# CommPosition_V1_0_Mar2016.net
KiCad netlist of a schematic drawn in EAGLE
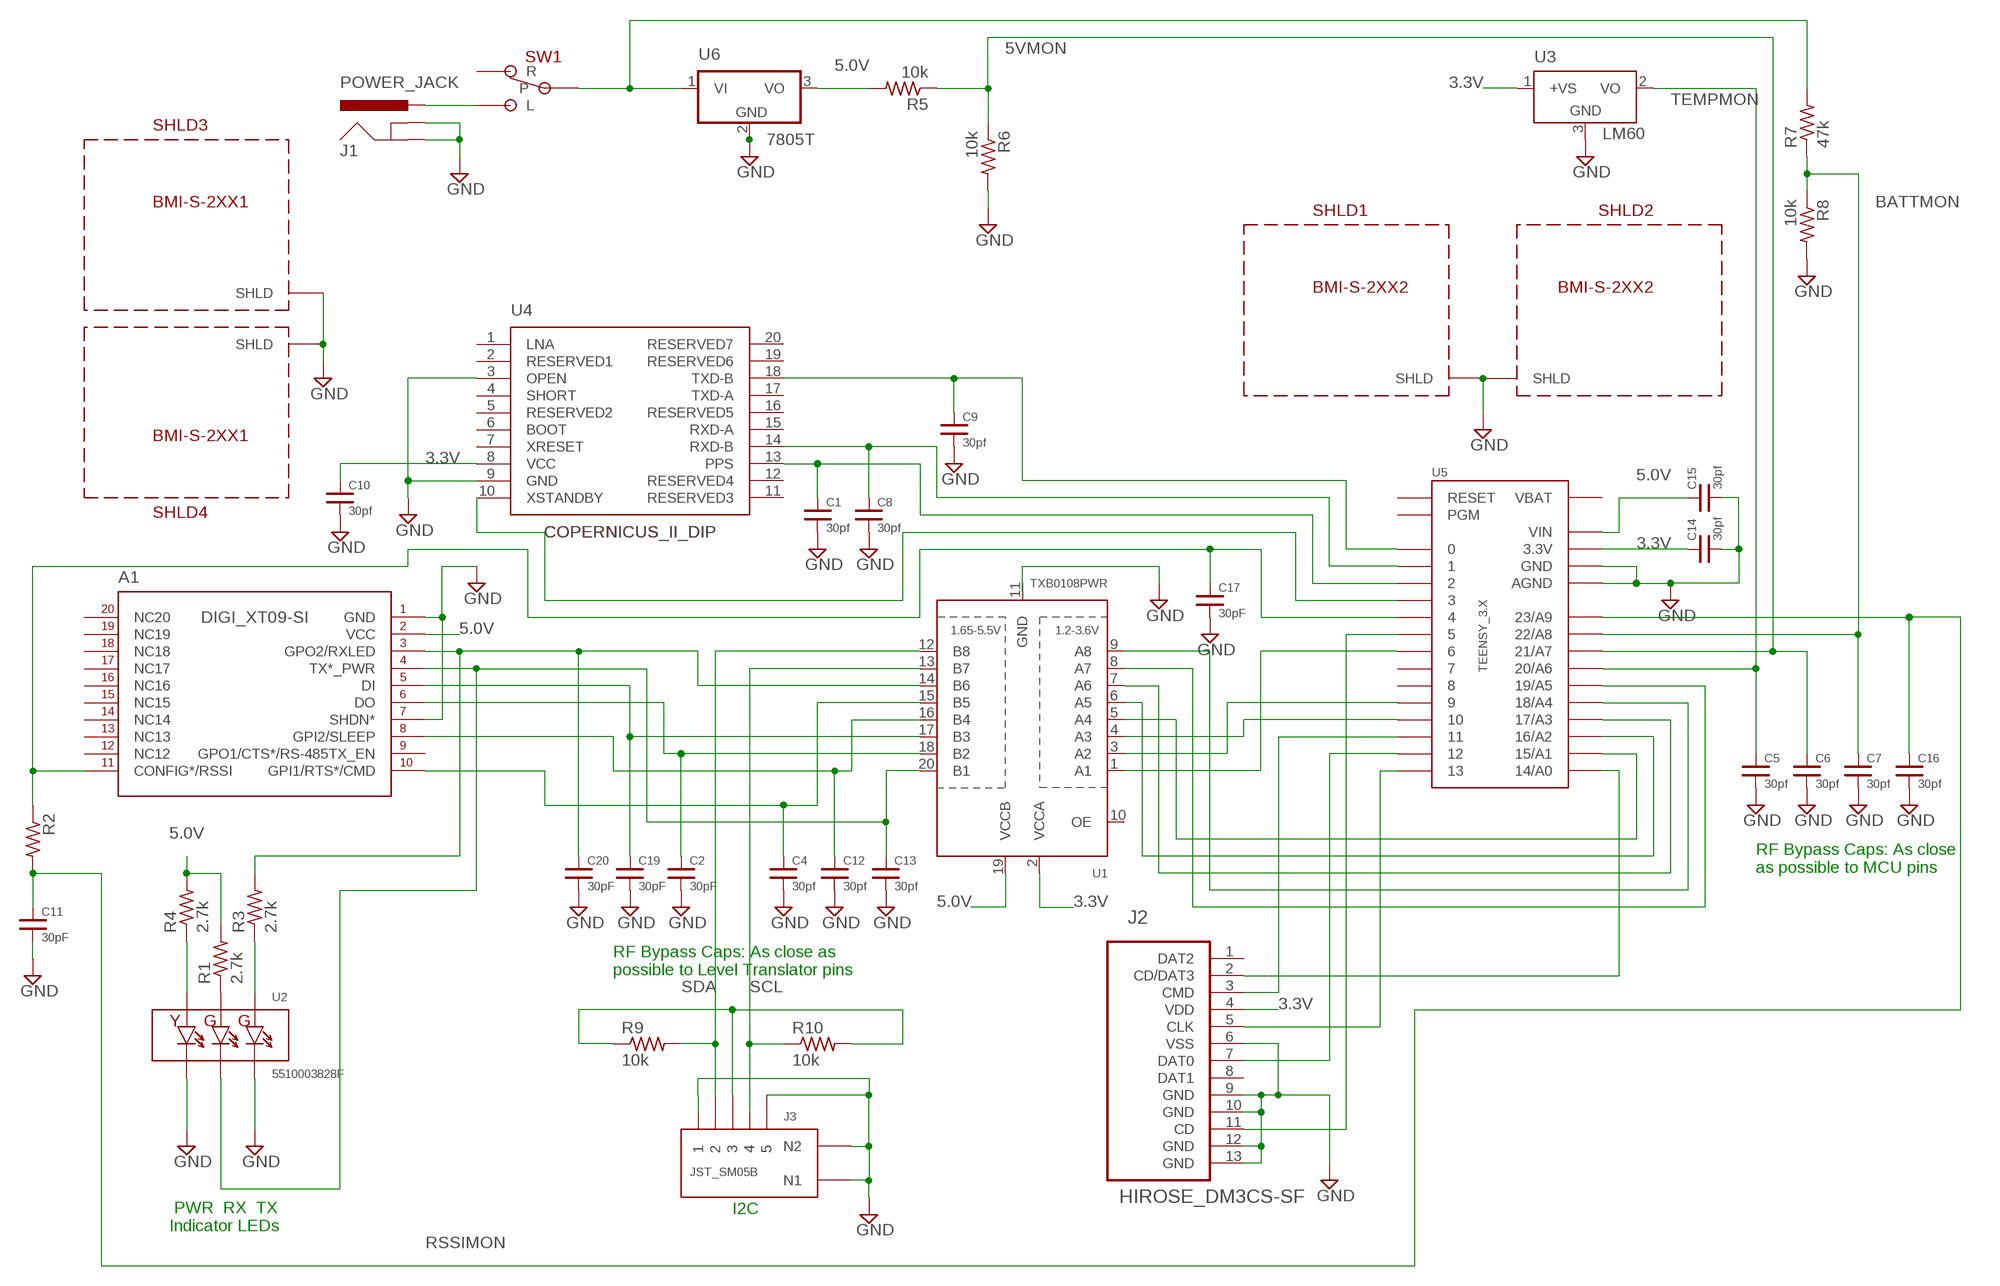
[diagram p0: schematic, sheet 1]

(export (version "E")
  (design (tool "Eeschema 10.0.6"))
  (components
    (comp (ref "A1")
      (value "DIGI_XT09-SI")
      (footprint "eagle-import:DIGI_XT09-SI")
      (libsource (lib "eagle-import") (part "DIGI_XT09-SI"))
    )
    (comp (ref "C1")
      (value "30pf")
      (footprint "eagle-import:C0603")
      (libsource (lib "eagle-import") (part "C-USC0603"))
    )
    (comp (ref "C2")
      (value "30pF")
      (footprint "eagle-import:C0603")
      (libsource (lib "eagle-import") (part "C-USC0603"))
    )
    (comp (ref "C4")
      (value "30pf")
      (footprint "eagle-import:C0603")
      (libsource (lib "eagle-import") (part "C-USC0603"))
    )
    (comp (ref "C5")
      (value "30pf")
      (footprint "eagle-import:C0603")
      (libsource (lib "eagle-import") (part "C-USC0603"))
    )
    (comp (ref "C6")
      (value "30pf")
      (footprint "eagle-import:C0603")
      (libsource (lib "eagle-import") (part "C-USC0603"))
    )
    (comp (ref "C7")
      (value "30pf")
      (footprint "eagle-import:C0603")
      (libsource (lib "eagle-import") (part "C-USC0603"))
    )
    (comp (ref "C8")
      (value "30pf")
      (footprint "eagle-import:C0603")
      (libsource (lib "eagle-import") (part "C-USC0603"))
    )
    (comp (ref "C9")
      (value "30pf")
      (footprint "eagle-import:C0603")
      (libsource (lib "eagle-import") (part "C-USC0603"))
    )
    (comp (ref "C10")
      (value "30pf")
      (footprint "eagle-import:C0603")
      (libsource (lib "eagle-import") (part "C-USC0603"))
    )
    (comp (ref "C11")
      (value "30pF")
      (footprint "eagle-import:C0603")
      (libsource (lib "eagle-import") (part "C-USC0603"))
    )
    (comp (ref "C12")
      (value "30pf")
      (footprint "eagle-import:C0603")
      (libsource (lib "eagle-import") (part "C-USC0603"))
    )
    (comp (ref "C13")
      (value "30pf")
      (footprint "eagle-import:C0603")
      (libsource (lib "eagle-import") (part "C-USC0603"))
    )
    (comp (ref "C14")
      (value "30pf")
      (footprint "eagle-import:C0603")
      (libsource (lib "eagle-import") (part "C-USC0603"))
    )
    (comp (ref "C15")
      (value "30pf")
      (footprint "eagle-import:C0603")
      (libsource (lib "eagle-import") (part "C-USC0603"))
    )
    (comp (ref "C16")
      (value "30pf")
      (footprint "eagle-import:C0603")
      (libsource (lib "eagle-import") (part "C-USC0603"))
    )
    (comp (ref "C17")
      (value "30pF")
      (footprint "eagle-import:C0603")
      (libsource (lib "eagle-import") (part "C-USC0603"))
    )
    (comp (ref "C19")
      (value "30pF")
      (footprint "eagle-import:C0603")
      (libsource (lib "eagle-import") (part "C-USC0603"))
    )
    (comp (ref "C20")
      (value "30pF")
      (footprint "eagle-import:C0603")
      (libsource (lib "eagle-import") (part "C-USC0603"))
    )
    (comp (ref "J1")
      (value "POWER_JACK")
      (footprint "eagle-import:PWR_JACK_BB")
      (libsource (lib "eagle-import") (part "POWER_JACK"))
    )
    (comp (ref "J2")
      (value "HIROSE_DM3CS-SF")
      (footprint "eagle-import:HIROSE_DM3CS-SF")
      (fields (field (name "MPN") "DM3CS-SF"))
      (libsource (lib "eagle-import") (part "HIROSE_DM3CS-SF"))
    )
    (comp (ref "J3")
      (value "JST_SM05B")
      (footprint "eagle-import:JST_SM05B")
      (libsource (lib "eagle-import") (part "JST_SM05B"))
    )
    (comp (ref "R1")
      (value "2.7k")
      (footprint "eagle-import:R0805")
      (libsource (lib "eagle-import") (part "R-US_R0805"))
    )
    (comp (ref "R2")
      (value "R-US_R0805")
      (footprint "eagle-import:R0805")
      (libsource (lib "eagle-import") (part "R-US_R0805"))
    )
    (comp (ref "R3")
      (value "2.7k")
      (footprint "eagle-import:R0805")
      (libsource (lib "eagle-import") (part "R-US_R0805"))
    )
    (comp (ref "R4")
      (value "2.7k")
      (footprint "eagle-import:R0805")
      (libsource (lib "eagle-import") (part "R-US_R0805"))
    )
    (comp (ref "R5")
      (value "10k")
      (footprint "eagle-import:R0805")
      (libsource (lib "eagle-import") (part "R-US_R0805"))
    )
    (comp (ref "R6")
      (value "10k")
      (footprint "eagle-import:R0805")
      (libsource (lib "eagle-import") (part "R-US_R0805"))
    )
    (comp (ref "R7")
      (value "47k")
      (footprint "eagle-import:R0805")
      (libsource (lib "eagle-import") (part "R-US_R0805"))
    )
    (comp (ref "R8")
      (value "10k")
      (footprint "eagle-import:R0805")
      (libsource (lib "eagle-import") (part "R-US_R0805"))
    )
    (comp (ref "R9")
      (value "10k")
      (footprint "eagle-import:R0805")
      (libsource (lib "eagle-import") (part "R-US_R0805"))
    )
    (comp (ref "R10")
      (value "10k")
      (footprint "eagle-import:R0805")
      (libsource (lib "eagle-import") (part "R-US_R0805"))
    )
    (comp (ref "SHLD1")
      (value "BMI-S-2XX2")
      (footprint "eagle-import:BMI-S-207-F")
      (libsource (lib "eagle-import") (part "BMI-S-2XX2"))
    )
    (comp (ref "SHLD2")
      (value "BMI-S-2XX2")
      (footprint "eagle-import:BMI-S-207-F")
      (libsource (lib "eagle-import") (part "BMI-S-2XX2"))
    )
    (comp (ref "SHLD3")
      (value "BMI-S-2XX1")
      (footprint "eagle-import:BMI-S-206-F")
      (libsource (lib "eagle-import") (part "BMI-S-2XX1"))
    )
    (comp (ref "SHLD4")
      (value "BMI-S-2XX1")
      (footprint "eagle-import:BMI-S-206-F")
      (libsource (lib "eagle-import") (part "BMI-S-2XX1"))
    )
    (comp (ref "SW1")
      (value "SPDT_RA_3A")
      (footprint "eagle-import:ESWITCH_SPDT_RA")
      (libsource (lib "eagle-import") (part "SPDT_RA_3A"))
    )
    (comp (ref "U1")
      (value "TXB0108PWR")
      (footprint "eagle-import:TSSOP20")
      (libsource (lib "eagle-import") (part "TXB0108PWR"))
    )
    (comp (ref "U2")
      (value "5510003828F")
      (footprint "eagle-import:TRIPLE_LED_SIDE_0.1IN")
      (libsource (lib "eagle-import") (part "5510003828F"))
    )
    (comp (ref "U3")
      (value "LM60")
      (footprint "eagle-import:TO92")
      (libsource (lib "eagle-import") (part "LM60"))
    )
    (comp (ref "U4")
      (value "COPERNICUS_II_DIP")
      (footprint "eagle-import:COPERNICUS_II_DIP")
      (libsource (lib "eagle-import") (part "COPERNICUS_II_DIP"))
    )
    (comp (ref "U5")
      (value "TEENSY_3.X")
      (footprint "eagle-import:TEENSY_3.X_PERIPHERY")
      (libsource (lib "eagle-import") (part "TEENSY_3.X"))
    )
    (comp (ref "U6")
      (value "7805T")
      (footprint "eagle-import:TO220H")
      (libsource (lib "eagle-import") (part "78T05"))
    )
  )
  (nets
    (net (code "1") (name "/3.3V") (class "Default")
      (node (ref "C10") (pin "1") (pinfunction "1_1") (pintype "passive"))
      (node (ref "C14") (pin "1") (pinfunction "1_1") (pintype "passive"))
      (node (ref "J2") (pin "4") (pinfunction "VDD_4") (pintype "passive"))
      (node (ref "U1") (pin "2") (pinfunction "VCCA_2") (pintype "bidirectional"))
      (node (ref "U3") (pin "1") (pinfunction "+VS_1") (pintype "input"))
      (node (ref "U4") (pin "8") (pinfunction "VCC_8") (pintype "bidirectional"))
      (node (ref "U5") (pin "3.3V") (pinfunction "3.3V_3.3V") (pintype "power_in"))
      (node (ref "U5") (pin "3.3V1") (pinfunction "3.3V_3.3V1") (pintype "power_in"))
    )
    (net (code "2") (name "/5.0V") (class "Default")
      (node (ref "A1") (pin "P$2") (pinfunction "VCC_P$2") (pintype "power_in"))
      (node (ref "C15") (pin "1") (pinfunction "1_1") (pintype "passive"))
      (node (ref "R1") (pin "2") (pinfunction "2_2") (pintype "passive"))
      (node (ref "R4") (pin "2") (pinfunction "2_2") (pintype "passive"))
      (node (ref "R5") (pin "2") (pinfunction "2_2") (pintype "passive"))
      (node (ref "U1") (pin "19") (pinfunction "VCCB_19") (pintype "bidirectional"))
      (node (ref "U5") (pin "VIN") (pinfunction "VIN_VIN") (pintype "input"))
      (node (ref "U6") (pin "3") (pinfunction "VO_3") (pintype "passive"))
    )
    (net (code "3") (name "/5VMON") (class "Default")
      (node (ref "C6") (pin "1") (pinfunction "1_1") (pintype "passive"))
      (node (ref "R5") (pin "1") (pinfunction "1_1") (pintype "passive"))
      (node (ref "R6") (pin "1") (pinfunction "1_1") (pintype "passive"))
      (node (ref "U5") (pin "21/A7") (pinfunction "21/A7_21/A7") (pintype "bidirectional"))
    )
    (net (code "4") (name "/BATTMON") (class "Default")
      (node (ref "C7") (pin "1") (pinfunction "1_1") (pintype "passive"))
      (node (ref "R7") (pin "1") (pinfunction "1_1") (pintype "passive"))
      (node (ref "R8") (pin "1") (pinfunction "1_1") (pintype "passive"))
      (node (ref "U5") (pin "22/A8") (pinfunction "22/A8_22/A8") (pintype "bidirectional"))
    )
    (net (code "5") (name "/RSSIMON") (class "Default")
      (node (ref "C11") (pin "1") (pinfunction "1_1") (pintype "passive"))
      (node (ref "C16") (pin "1") (pinfunction "1_1") (pintype "passive"))
      (node (ref "R2") (pin "2") (pinfunction "2_2") (pintype "passive"))
      (node (ref "U5") (pin "23/A9") (pinfunction "23/A9_23/A9") (pintype "bidirectional"))
    )
    (net (code "6") (name "/SCL") (class "Default")
      (node (ref "J3") (pin "P$4") (pinfunction "4_P$4") (pintype "bidirectional"))
      (node (ref "R10") (pin "1") (pinfunction "1_1") (pintype "passive"))
      (node (ref "U1") (pin "13") (pinfunction "B7_13") (pintype "bidirectional"))
    )
    (net (code "7") (name "/SDA") (class "Default")
      (node (ref "J3") (pin "P$2") (pinfunction "2_P$2") (pintype "bidirectional"))
      (node (ref "R9") (pin "2") (pinfunction "2_2") (pintype "passive"))
      (node (ref "U1") (pin "12") (pinfunction "B8_12") (pintype "bidirectional"))
    )
    (net (code "8") (name "/TEMPMON") (class "Default")
      (node (ref "C5") (pin "1") (pinfunction "1_1") (pintype "passive"))
      (node (ref "U3") (pin "2") (pinfunction "VO_2") (pintype "input"))
      (node (ref "U5") (pin "20/A6") (pinfunction "20/A6_20/A6") (pintype "bidirectional"))
    )
    (net (code "9") (name "GND") (class "Default")
      (node (ref "A1") (pin "P$1") (pinfunction "GND_P$1") (pintype "power_in"))
      (node (ref "A1") (pin "P$21") (pinfunction "GND_P$21") (pintype "power_in"))
      (node (ref "A1") (pin "P$22") (pinfunction "GND_P$22") (pintype "power_in"))
      (node (ref "A1") (pin "P$23") (pinfunction "GND_P$23") (pintype "power_in"))
      (node (ref "A1") (pin "P$24") (pinfunction "GND_P$24") (pintype "power_in"))
      (node (ref "A1") (pin "P$7") (pinfunction "SHDN*_P$7") (pintype "input"))
      (node (ref "C1") (pin "2") (pinfunction "2_2") (pintype "passive"))
      (node (ref "C10") (pin "2") (pinfunction "2_2") (pintype "passive"))
      (node (ref "C11") (pin "2") (pinfunction "2_2") (pintype "passive"))
      (node (ref "C12") (pin "2") (pinfunction "2_2") (pintype "passive"))
      (node (ref "C13") (pin "2") (pinfunction "2_2") (pintype "passive"))
      (node (ref "C14") (pin "2") (pinfunction "2_2") (pintype "passive"))
      (node (ref "C15") (pin "2") (pinfunction "2_2") (pintype "passive"))
      (node (ref "C16") (pin "2") (pinfunction "2_2") (pintype "passive"))
      (node (ref "C17") (pin "2") (pinfunction "2_2") (pintype "passive"))
      (node (ref "C19") (pin "2") (pinfunction "2_2") (pintype "passive"))
      (node (ref "C2") (pin "2") (pinfunction "2_2") (pintype "passive"))
      (node (ref "C20") (pin "2") (pinfunction "2_2") (pintype "passive"))
      (node (ref "C4") (pin "2") (pinfunction "2_2") (pintype "passive"))
      (node (ref "C5") (pin "2") (pinfunction "2_2") (pintype "passive"))
      (node (ref "C6") (pin "2") (pinfunction "2_2") (pintype "passive"))
      (node (ref "C7") (pin "2") (pinfunction "2_2") (pintype "passive"))
      (node (ref "C8") (pin "2") (pinfunction "2_2") (pintype "passive"))
      (node (ref "C9") (pin "2") (pinfunction "2_2") (pintype "passive"))
      (node (ref "J1") (pin "GND") (pinfunction "GND_GND") (pintype "bidirectional"))
      (node (ref "J1") (pin "GNDBREAK") (pinfunction "GNDBREAK_GNDBREAK") (pintype "bidirectional"))
      (node (ref "J2") (pin "10") (pinfunction "GND_10") (pintype "passive"))
      (node (ref "J2") (pin "12") (pinfunction "GND_12") (pintype "passive"))
      (node (ref "J2") (pin "13") (pinfunction "GND_13") (pintype "passive"))
      (node (ref "J2") (pin "6") (pinfunction "VSS_6") (pintype "passive"))
      (node (ref "J2") (pin "9") (pinfunction "GND_9") (pintype "passive"))
      (node (ref "J3") (pin "P$1") (pinfunction "1_P$1") (pintype "bidirectional"))
      (node (ref "J3") (pin "P$5") (pinfunction "5_P$5") (pintype "bidirectional"))
      (node (ref "J3") (pin "P$6") (pinfunction "N1_P$6") (pintype "bidirectional"))
      (node (ref "J3") (pin "P$7") (pinfunction "N2_P$7") (pintype "bidirectional"))
      (node (ref "R6") (pin "2") (pinfunction "2_2") (pintype "passive"))
      (node (ref "R8") (pin "2") (pinfunction "2_2") (pintype "passive"))
      (node (ref "SHLD1") (pin "P$10") (pinfunction "SHLD_P$10") (pintype "bidirectional"))
      (node (ref "SHLD1") (pin "P$11") (pinfunction "SHLD_P$11") (pintype "bidirectional"))
      (node (ref "SHLD1") (pin "P$12") (pinfunction "SHLD_P$12") (pintype "bidirectional"))
      (node (ref "SHLD1") (pin "P$14") (pinfunction "SHLD_P$14") (pintype "bidirectional"))
      (node (ref "SHLD1") (pin "P$15") (pinfunction "SHLD_P$15") (pintype "bidirectional"))
      (node (ref "SHLD1") (pin "P$16") (pinfunction "SHLD_P$16") (pintype "bidirectional"))
      (node (ref "SHLD1") (pin "P$17") (pinfunction "SHLD_P$17") (pintype "bidirectional"))
      (node (ref "SHLD1") (pin "P$18") (pinfunction "SHLD_P$18") (pintype "bidirectional"))
      (node (ref "SHLD1") (pin "P$19") (pinfunction "SHLD_P$19") (pintype "bidirectional"))
      (node (ref "SHLD1") (pin "P$2") (pinfunction "SHLD_P$2") (pintype "bidirectional"))
      (node (ref "SHLD1") (pin "P$20") (pinfunction "SHLD_P$20") (pintype "bidirectional"))
      (node (ref "SHLD1") (pin "P$21") (pinfunction "SHLD_P$21") (pintype "bidirectional"))
      (node (ref "SHLD1") (pin "P$22") (pinfunction "SHLD_P$22") (pintype "bidirectional"))
      (node (ref "SHLD1") (pin "P$23") (pinfunction "SHLD_P$23") (pintype "bidirectional"))
      (node (ref "SHLD1") (pin "P$24") (pinfunction "SHLD_P$24") (pintype "bidirectional"))
      (node (ref "SHLD1") (pin "P$25") (pinfunction "SHLD_P$25") (pintype "bidirectional"))
      (node (ref "SHLD1") (pin "P$26") (pinfunction "SHLD_P$26") (pintype "bidirectional"))
      (node (ref "SHLD1") (pin "P$27") (pinfunction "SHLD_P$27") (pintype "bidirectional"))
      (node (ref "SHLD1") (pin "P$28") (pinfunction "SHLD_P$28") (pintype "bidirectional"))
      (node (ref "SHLD1") (pin "P$29") (pinfunction "SHLD_P$29") (pintype "bidirectional"))
      (node (ref "SHLD1") (pin "P$3") (pinfunction "SHLD_P$3") (pintype "bidirectional"))
      (node (ref "SHLD1") (pin "P$30") (pinfunction "SHLD_P$30") (pintype "bidirectional"))
      (node (ref "SHLD1") (pin "P$31") (pinfunction "SHLD_P$31") (pintype "bidirectional"))
      (node (ref "SHLD1") (pin "P$32") (pinfunction "SHLD_P$32") (pintype "bidirectional"))
      (node (ref "SHLD1") (pin "P$33") (pinfunction "SHLD_P$33") (pintype "bidirectional"))
      (node (ref "SHLD1") (pin "P$34") (pinfunction "SHLD_P$34") (pintype "bidirectional"))
      (node (ref "SHLD1") (pin "P$4") (pinfunction "SHLD_P$4") (pintype "bidirectional"))
      (node (ref "SHLD1") (pin "P$5") (pinfunction "SHLD_P$5") (pintype "bidirectional"))
      (node (ref "SHLD1") (pin "P$6") (pinfunction "SHLD_P$6") (pintype "bidirectional"))
      (node (ref "SHLD1") (pin "P$7") (pinfunction "SHLD_P$7") (pintype "bidirectional"))
      (node (ref "SHLD1") (pin "P$8") (pinfunction "SHLD_P$8") (pintype "bidirectional"))
      (node (ref "SHLD1") (pin "P$9") (pinfunction "SHLD_P$9") (pintype "bidirectional"))
      (node (ref "SHLD2") (pin "P$10") (pinfunction "SHLD_P$10") (pintype "bidirectional"))
      (node (ref "SHLD2") (pin "P$11") (pinfunction "SHLD_P$11") (pintype "bidirectional"))
      (node (ref "SHLD2") (pin "P$12") (pinfunction "SHLD_P$12") (pintype "bidirectional"))
      (node (ref "SHLD2") (pin "P$14") (pinfunction "SHLD_P$14") (pintype "bidirectional"))
      (node (ref "SHLD2") (pin "P$15") (pinfunction "SHLD_P$15") (pintype "bidirectional"))
      (node (ref "SHLD2") (pin "P$16") (pinfunction "SHLD_P$16") (pintype "bidirectional"))
      (node (ref "SHLD2") (pin "P$17") (pinfunction "SHLD_P$17") (pintype "bidirectional"))
      (node (ref "SHLD2") (pin "P$18") (pinfunction "SHLD_P$18") (pintype "bidirectional"))
      (node (ref "SHLD2") (pin "P$19") (pinfunction "SHLD_P$19") (pintype "bidirectional"))
      (node (ref "SHLD2") (pin "P$2") (pinfunction "SHLD_P$2") (pintype "bidirectional"))
      (node (ref "SHLD2") (pin "P$20") (pinfunction "SHLD_P$20") (pintype "bidirectional"))
      (node (ref "SHLD2") (pin "P$21") (pinfunction "SHLD_P$21") (pintype "bidirectional"))
      (node (ref "SHLD2") (pin "P$22") (pinfunction "SHLD_P$22") (pintype "bidirectional"))
      (node (ref "SHLD2") (pin "P$23") (pinfunction "SHLD_P$23") (pintype "bidirectional"))
      (node (ref "SHLD2") (pin "P$24") (pinfunction "SHLD_P$24") (pintype "bidirectional"))
      (node (ref "SHLD2") (pin "P$25") (pinfunction "SHLD_P$25") (pintype "bidirectional"))
      (node (ref "SHLD2") (pin "P$26") (pinfunction "SHLD_P$26") (pintype "bidirectional"))
      (node (ref "SHLD2") (pin "P$27") (pinfunction "SHLD_P$27") (pintype "bidirectional"))
      (node (ref "SHLD2") (pin "P$28") (pinfunction "SHLD_P$28") (pintype "bidirectional"))
      (node (ref "SHLD2") (pin "P$29") (pinfunction "SHLD_P$29") (pintype "bidirectional"))
      (node (ref "SHLD2") (pin "P$3") (pinfunction "SHLD_P$3") (pintype "bidirectional"))
      (node (ref "SHLD2") (pin "P$30") (pinfunction "SHLD_P$30") (pintype "bidirectional"))
      (node (ref "SHLD2") (pin "P$31") (pinfunction "SHLD_P$31") (pintype "bidirectional"))
      (node (ref "SHLD2") (pin "P$32") (pinfunction "SHLD_P$32") (pintype "bidirectional"))
      (node (ref "SHLD2") (pin "P$33") (pinfunction "SHLD_P$33") (pintype "bidirectional"))
      (node (ref "SHLD2") (pin "P$34") (pinfunction "SHLD_P$34") (pintype "bidirectional"))
      (node (ref "SHLD2") (pin "P$4") (pinfunction "SHLD_P$4") (pintype "bidirectional"))
      (node (ref "SHLD2") (pin "P$5") (pinfunction "SHLD_P$5") (pintype "bidirectional"))
      (node (ref "SHLD2") (pin "P$6") (pinfunction "SHLD_P$6") (pintype "bidirectional"))
      (node (ref "SHLD2") (pin "P$7") (pinfunction "SHLD_P$7") (pintype "bidirectional"))
      (node (ref "SHLD2") (pin "P$8") (pinfunction "SHLD_P$8") (pintype "bidirectional"))
      (node (ref "SHLD2") (pin "P$9") (pinfunction "SHLD_P$9") (pintype "bidirectional"))
      (node (ref "SHLD3") (pin "P$1") (pinfunction "SHLD_P$1") (pintype "bidirectional"))
      (node (ref "SHLD3") (pin "P$10") (pinfunction "SHLD_P$10") (pintype "bidirectional"))
      (node (ref "SHLD3") (pin "P$11") (pinfunction "SHLD_P$11") (pintype "bidirectional"))
      (node (ref "SHLD3") (pin "P$12") (pinfunction "SHLD_P$12") (pintype "bidirectional"))
      (node (ref "SHLD3") (pin "P$14") (pinfunction "SHLD_P$14") (pintype "bidirectional"))
      (node (ref "SHLD3") (pin "P$15") (pinfunction "SHLD_P$15") (pintype "bidirectional"))
      (node (ref "SHLD3") (pin "P$16") (pinfunction "SHLD_P$16") (pintype "bidirectional"))
      (node (ref "SHLD3") (pin "P$17") (pinfunction "SHLD_P$17") (pintype "bidirectional"))
      (node (ref "SHLD3") (pin "P$18") (pinfunction "SHLD_P$18") (pintype "bidirectional"))
      (node (ref "SHLD3") (pin "P$2") (pinfunction "SHLD_P$2") (pintype "bidirectional"))
      (node (ref "SHLD3") (pin "P$21") (pinfunction "SHLD_P$21") (pintype "bidirectional"))
      (node (ref "SHLD3") (pin "P$22") (pinfunction "SHLD_P$22") (pintype "bidirectional"))
      (node (ref "SHLD3") (pin "P$23") (pinfunction "SHLD_P$23") (pintype "bidirectional"))
      (node (ref "SHLD3") (pin "P$24") (pinfunction "SHLD_P$24") (pintype "bidirectional"))
      (node (ref "SHLD3") (pin "P$25") (pinfunction "SHLD_P$25") (pintype "bidirectional"))
      (node (ref "SHLD3") (pin "P$3") (pinfunction "SHLD_P$3") (pintype "bidirectional"))
      (node (ref "SHLD3") (pin "P$31") (pinfunction "SHLD_P$31") (pintype "bidirectional"))
      (node (ref "SHLD3") (pin "P$32") (pinfunction "SHLD_P$32") (pintype "bidirectional"))
      (node (ref "SHLD3") (pin "P$4") (pinfunction "SHLD_P$4") (pintype "bidirectional"))
      (node (ref "SHLD3") (pin "P$5") (pinfunction "SHLD_P$5") (pintype "bidirectional"))
      (node (ref "SHLD3") (pin "P$6") (pinfunction "SHLD_P$6") (pintype "bidirectional"))
      (node (ref "SHLD3") (pin "P$7") (pinfunction "SHLD_P$7") (pintype "bidirectional"))
      (node (ref "SHLD3") (pin "P$8") (pinfunction "SHLD_P$8") (pintype "bidirectional"))
      (node (ref "SHLD3") (pin "P$9") (pinfunction "SHLD_P$9") (pintype "bidirectional"))
      (node (ref "SHLD4") (pin "P$1") (pinfunction "SHLD_P$1") (pintype "bidirectional"))
      (node (ref "SHLD4") (pin "P$10") (pinfunction "SHLD_P$10") (pintype "bidirectional"))
      (node (ref "SHLD4") (pin "P$11") (pinfunction "SHLD_P$11") (pintype "bidirectional"))
      (node (ref "SHLD4") (pin "P$12") (pinfunction "SHLD_P$12") (pintype "bidirectional"))
      (node (ref "SHLD4") (pin "P$14") (pinfunction "SHLD_P$14") (pintype "bidirectional"))
      (node (ref "SHLD4") (pin "P$15") (pinfunction "SHLD_P$15") (pintype "bidirectional"))
      (node (ref "SHLD4") (pin "P$16") (pinfunction "SHLD_P$16") (pintype "bidirectional"))
      (node (ref "SHLD4") (pin "P$17") (pinfunction "SHLD_P$17") (pintype "bidirectional"))
      (node (ref "SHLD4") (pin "P$18") (pinfunction "SHLD_P$18") (pintype "bidirectional"))
      (node (ref "SHLD4") (pin "P$2") (pinfunction "SHLD_P$2") (pintype "bidirectional"))
      (node (ref "SHLD4") (pin "P$21") (pinfunction "SHLD_P$21") (pintype "bidirectional"))
      (node (ref "SHLD4") (pin "P$22") (pinfunction "SHLD_P$22") (pintype "bidirectional"))
      (node (ref "SHLD4") (pin "P$23") (pinfunction "SHLD_P$23") (pintype "bidirectional"))
      (node (ref "SHLD4") (pin "P$24") (pinfunction "SHLD_P$24") (pintype "bidirectional"))
      (node (ref "SHLD4") (pin "P$25") (pinfunction "SHLD_P$25") (pintype "bidirectional"))
      (node (ref "SHLD4") (pin "P$3") (pinfunction "SHLD_P$3") (pintype "bidirectional"))
      (node (ref "SHLD4") (pin "P$31") (pinfunction "SHLD_P$31") (pintype "bidirectional"))
      (node (ref "SHLD4") (pin "P$32") (pinfunction "SHLD_P$32") (pintype "bidirectional"))
      (node (ref "SHLD4") (pin "P$4") (pinfunction "SHLD_P$4") (pintype "bidirectional"))
      (node (ref "SHLD4") (pin "P$5") (pinfunction "SHLD_P$5") (pintype "bidirectional"))
      (node (ref "SHLD4") (pin "P$6") (pinfunction "SHLD_P$6") (pintype "bidirectional"))
      (node (ref "SHLD4") (pin "P$7") (pinfunction "SHLD_P$7") (pintype "bidirectional"))
      (node (ref "SHLD4") (pin "P$8") (pinfunction "SHLD_P$8") (pintype "bidirectional"))
      (node (ref "SHLD4") (pin "P$9") (pinfunction "SHLD_P$9") (pintype "bidirectional"))
      (node (ref "U1") (pin "11") (pinfunction "GND_11") (pintype "bidirectional"))
      (node (ref "U2") (pin "P$1") (pinfunction "1_P$1") (pintype "bidirectional"))
      (node (ref "U2") (pin "P$5") (pinfunction "5_P$5") (pintype "bidirectional"))
      (node (ref "U3") (pin "3") (pinfunction "GND_3") (pintype "power_in"))
      (node (ref "U4") (pin "3") (pinfunction "OPEN_3") (pintype "bidirectional"))
      (node (ref "U4") (pin "9") (pinfunction "GND_9") (pintype "bidirectional"))
      (node (ref "U5") (pin "AGND") (pinfunction "AGND_AGND") (pintype "power_in"))
      (node (ref "U5") (pin "GND") (pinfunction "GND_GND") (pintype "power_in"))
      (node (ref "U5") (pin "GND1") (pinfunction "GND_GND1") (pintype "power_in"))
      (node (ref "U6") (pin "2") (pinfunction "GND_2") (pintype "passive"))
    )
    (net (code "10") (name "Net-(A1-CONFIG*{slash}RSSI)") (class "Default")
      (node (ref "A1") (pin "P$11") (pinfunction "CONFIG*/RSSI_P$11") (pintype "bidirectional"))
      (node (ref "C17") (pin "1") (pinfunction "1_1") (pintype "passive"))
      (node (ref "R2") (pin "1") (pinfunction "1_1") (pintype "passive"))
      (node (ref "U5") (pin "4") (pinfunction "4_4") (pintype "bidirectional"))
    )
    (net (code "11") (name "Net-(A1-DI)") (class "Default")
      (node (ref "A1") (pin "P$5") (pinfunction "DI_P$5") (pintype "bidirectional"))
      (node (ref "C19") (pin "1") (pinfunction "1_1") (pintype "passive"))
      (node (ref "U1") (pin "17") (pinfunction "B3_17") (pintype "bidirectional"))
    )
    (net (code "12") (name "Net-(A1-DO)") (class "Default")
      (node (ref "A1") (pin "P$6") (pinfunction "DO_P$6") (pintype "output"))
      (node (ref "C2") (pin "1") (pinfunction "1_1") (pintype "passive"))
      (node (ref "U1") (pin "18") (pinfunction "B2_18") (pintype "bidirectional"))
    )
    (net (code "13") (name "Net-(A1-GPI1{slash}RTS*{slash}CMD)") (class "Default")
      (node (ref "A1") (pin "P$10") (pinfunction "GPI1/RTS*/CMD_P$10") (pintype "input"))
      (node (ref "C4") (pin "1") (pinfunction "1_1") (pintype "passive"))
      (node (ref "U1") (pin "15") (pinfunction "B5_15") (pintype "bidirectional"))
    )
    (net (code "14") (name "Net-(A1-GPI2{slash}SLEEP)") (class "Default")
      (node (ref "A1") (pin "P$8") (pinfunction "GPI2/SLEEP_P$8") (pintype "input"))
      (node (ref "C12") (pin "1") (pinfunction "1_1") (pintype "passive"))
      (node (ref "U1") (pin "16") (pinfunction "B4_16") (pintype "bidirectional"))
    )
    (net (code "15") (name "Net-(A1-GPO2{slash}RXLED)") (class "Default")
      (node (ref "A1") (pin "P$3") (pinfunction "GPO2/RXLED_P$3") (pintype "input"))
      (node (ref "C20") (pin "1") (pinfunction "1_1") (pintype "passive"))
      (node (ref "R3") (pin "2") (pinfunction "2_2") (pintype "passive"))
      (node (ref "U1") (pin "14") (pinfunction "B6_14") (pintype "bidirectional"))
    )
    (net (code "16") (name "Net-(A1-TX*_PWR)") (class "Default")
      (node (ref "A1") (pin "P$4") (pinfunction "TX*_PWR_P$4") (pintype "output"))
      (node (ref "C13") (pin "1") (pinfunction "1_1") (pintype "passive"))
      (node (ref "U1") (pin "20") (pinfunction "B1_20") (pintype "bidirectional"))
      (node (ref "U2") (pin "P$3") (pinfunction "3_P$3") (pintype "bidirectional"))
    )
    (net (code "17") (name "Net-(J2-CD)") (class "Default")
      (node (ref "J2") (pin "11") (pinfunction "CD_11") (pintype "passive"))
      (node (ref "U5") (pin "5") (pinfunction "5_5") (pintype "bidirectional"))
    )
    (net (code "18") (name "Net-(J2-CD{slash}DAT3)") (class "Default")
      (node (ref "J2") (pin "2") (pinfunction "CD/DAT3_2") (pintype "passive"))
      (node (ref "U5") (pin "14/A0") (pinfunction "14/A0_14/A0") (pintype "bidirectional"))
    )
    (net (code "19") (name "Net-(J2-CLK)") (class "Default")
      (node (ref "J2") (pin "5") (pinfunction "CLK_5") (pintype "passive"))
      (node (ref "U5") (pin "13") (pinfunction "13_13") (pintype "bidirectional"))
    )
    (net (code "20") (name "Net-(J2-CMD)") (class "Default")
      (node (ref "J2") (pin "3") (pinfunction "CMD_3") (pintype "passive"))
      (node (ref "U5") (pin "11") (pinfunction "11_11") (pintype "bidirectional"))
    )
    (net (code "21") (name "Net-(J2-DAT0)") (class "Default")
      (node (ref "J2") (pin "7") (pinfunction "DAT0_7") (pintype "passive"))
      (node (ref "U5") (pin "12") (pinfunction "12_12") (pintype "bidirectional"))
    )
    (net (code "22") (name "Net-(J3-3)") (class "Default")
      (node (ref "J3") (pin "P$3") (pinfunction "3_P$3") (pintype "bidirectional"))
      (node (ref "R10") (pin "2") (pinfunction "2_2") (pintype "passive"))
      (node (ref "R9") (pin "1") (pinfunction "1_1") (pintype "passive"))
    )
    (net (code "23") (name "Net-(SW1-L)") (class "Default")
      (node (ref "J1") (pin "PWR") (pinfunction "PWR_PWR") (pintype "bidirectional"))
      (node (ref "SW1") (pin "P$1") (pinfunction "L_P$1") (pintype "bidirectional"))
    )
    (net (code "24") (name "Net-(SW1-P)") (class "Default")
      (node (ref "R7") (pin "2") (pinfunction "2_2") (pintype "passive"))
      (node (ref "SW1") (pin "P$2") (pinfunction "P_P$2") (pintype "bidirectional"))
      (node (ref "U6") (pin "1") (pinfunction "VI_1") (pintype "input"))
    )
    (net (code "25") (name "Net-(U1-A1)") (class "Default")
      (node (ref "U1") (pin "1") (pinfunction "A1_1") (pintype "bidirectional"))
      (node (ref "U5") (pin "6") (pinfunction "6_6") (pintype "bidirectional"))
    )
    (net (code "26") (name "Net-(U1-A2)") (class "Default")
      (node (ref "U1") (pin "3") (pinfunction "A2_3") (pintype "bidirectional"))
      (node (ref "U5") (pin "9") (pinfunction "9_9") (pintype "bidirectional"))
    )
    (net (code "27") (name "Net-(U1-A3)") (class "Default")
      (node (ref "U1") (pin "4") (pinfunction "A3_4") (pintype "bidirectional"))
      (node (ref "U5") (pin "10") (pinfunction "10_10") (pintype "bidirectional"))
    )
    (net (code "28") (name "Net-(U1-A4)") (class "Default")
      (node (ref "U1") (pin "5") (pinfunction "A4_5") (pintype "bidirectional"))
      (node (ref "U5") (pin "15/A1") (pinfunction "15/A1_15/A1") (pintype "bidirectional"))
    )
    (net (code "29") (name "Net-(U1-A5)") (class "Default")
      (node (ref "U1") (pin "6") (pinfunction "A5_6") (pintype "bidirectional"))
      (node (ref "U5") (pin "16/A2") (pinfunction "16/A2_16/A2") (pintype "bidirectional"))
    )
    (net (code "30") (name "Net-(U1-A6)") (class "Default")
      (node (ref "U1") (pin "7") (pinfunction "A6_7") (pintype "bidirectional"))
      (node (ref "U5") (pin "17/A3") (pinfunction "17/A3_17/A3") (pintype "bidirectional"))
    )
    (net (code "31") (name "Net-(U1-A7)") (class "Default")
      (node (ref "U1") (pin "8") (pinfunction "A7_8") (pintype "bidirectional"))
      (node (ref "U5") (pin "19/A5") (pinfunction "19/A5_19/A5") (pintype "bidirectional"))
    )
    (net (code "32") (name "Net-(U1-A8)") (class "Default")
      (node (ref "U1") (pin "9") (pinfunction "A8_9") (pintype "bidirectional"))
      (node (ref "U5") (pin "18/A4") (pinfunction "18/A4_18/A4") (pintype "bidirectional"))
    )
    (net (code "33") (name "Net-(U2-2)") (class "Default")
      (node (ref "R3") (pin "1") (pinfunction "1_1") (pintype "passive"))
      (node (ref "U2") (pin "P$2") (pinfunction "2_P$2") (pintype "bidirectional"))
    )
    (net (code "34") (name "Net-(U2-4)") (class "Default")
      (node (ref "R1") (pin "1") (pinfunction "1_1") (pintype "passive"))
      (node (ref "U2") (pin "P$4") (pinfunction "4_P$4") (pintype "bidirectional"))
    )
    (net (code "35") (name "Net-(U2-6)") (class "Default")
      (node (ref "R4") (pin "1") (pinfunction "1_1") (pintype "passive"))
      (node (ref "U2") (pin "P$6") (pinfunction "6_P$6") (pintype "bidirectional"))
    )
    (net (code "36") (name "Net-(U4-PPS)") (class "Default")
      (node (ref "C1") (pin "1") (pinfunction "1_1") (pintype "passive"))
      (node (ref "U4") (pin "13") (pinfunction "PPS_13") (pintype "bidirectional"))
      (node (ref "U5") (pin "2") (pinfunction "2_2") (pintype "bidirectional"))
    )
    (net (code "37") (name "Net-(U4-RXD-B)") (class "Default")
      (node (ref "C8") (pin "1") (pinfunction "1_1") (pintype "passive"))
      (node (ref "U4") (pin "14") (pinfunction "RXD-B_14") (pintype "bidirectional"))
      (node (ref "U5") (pin "1") (pinfunction "1_1") (pintype "bidirectional"))
    )
    (net (code "38") (name "Net-(U4-TXD-B)") (class "Default")
      (node (ref "C9") (pin "1") (pinfunction "1_1") (pintype "passive"))
      (node (ref "U4") (pin "18") (pinfunction "TXD-B_18") (pintype "bidirectional"))
      (node (ref "U5") (pin "0") (pinfunction "0_0") (pintype "bidirectional"))
    )
    (net (code "39") (name "Net-(U4-XSTANDBY)") (class "Default")
      (node (ref "U4") (pin "10") (pinfunction "XSTANDBY_10") (pintype "bidirectional"))
      (node (ref "U5") (pin "3") (pinfunction "3_3") (pintype "bidirectional"))
    )
    (net (code "40") (name "unconnected-(A1-GPO1{slash}CTS*{slash}RS-485TX_EN-PadP$9)") (class "Default")
      (node (ref "A1") (pin "P$9") (pinfunction "GPO1/CTS*/RS-485TX_EN_P$9") (pintype "output"))
    )
    (net (code "41") (name "unconnected-(A1-NC12-PadP$12)") (class "Default")
      (node (ref "A1") (pin "P$12") (pinfunction "NC12_P$12") (pintype "no_connect"))
    )
    (net (code "42") (name "unconnected-(A1-NC13-PadP$13)") (class "Default")
      (node (ref "A1") (pin "P$13") (pinfunction "NC13_P$13") (pintype "no_connect"))
    )
    (net (code "43") (name "unconnected-(A1-NC14-PadP$14)") (class "Default")
      (node (ref "A1") (pin "P$14") (pinfunction "NC14_P$14") (pintype "no_connect"))
    )
    (net (code "44") (name "unconnected-(A1-NC15-PadP$15)") (class "Default")
      (node (ref "A1") (pin "P$15") (pinfunction "NC15_P$15") (pintype "no_connect"))
    )
    (net (code "45") (name "unconnected-(A1-NC16-PadP$16)") (class "Default")
      (node (ref "A1") (pin "P$16") (pinfunction "NC16_P$16") (pintype "no_connect"))
    )
    (net (code "46") (name "unconnected-(A1-NC17-PadP$17)") (class "Default")
      (node (ref "A1") (pin "P$17") (pinfunction "NC17_P$17") (pintype "no_connect"))
    )
    (net (code "47") (name "unconnected-(A1-NC18-PadP$18)") (class "Default")
      (node (ref "A1") (pin "P$18") (pinfunction "NC18_P$18") (pintype "no_connect"))
    )
    (net (code "48") (name "unconnected-(A1-NC19-PadP$19)") (class "Default")
      (node (ref "A1") (pin "P$19") (pinfunction "NC19_P$19") (pintype "no_connect"))
    )
    (net (code "49") (name "unconnected-(A1-NC20-PadP$20)") (class "Default")
      (node (ref "A1") (pin "P$20") (pinfunction "NC20_P$20") (pintype "no_connect"))
    )
    (net (code "50") (name "unconnected-(J2-DAT1-Pad8)") (class "Default")
      (node (ref "J2") (pin "8") (pinfunction "DAT1_8") (pintype "passive"))
    )
    (net (code "51") (name "unconnected-(J2-DAT2-Pad1)") (class "Default")
      (node (ref "J2") (pin "1") (pinfunction "DAT2_1") (pintype "passive"))
    )
    (net (code "52") (name "unconnected-(SW1-R-PadP$3)") (class "Default")
      (node (ref "SW1") (pin "P$3") (pinfunction "R_P$3") (pintype "bidirectional"))
    )
    (net (code "53") (name "unconnected-(U1-OE-Pad10)") (class "Default")
      (node (ref "U1") (pin "10") (pinfunction "OE_10") (pintype "bidirectional"))
    )
    (net (code "54") (name "unconnected-(U4-BOOT-Pad6)") (class "Default")
      (node (ref "U4") (pin "6") (pinfunction "BOOT_6") (pintype "bidirectional"))
    )
    (net (code "55") (name "unconnected-(U4-LNA-Pad1)") (class "Default")
      (node (ref "U4") (pin "1") (pinfunction "LNA_1") (pintype "bidirectional"))
    )
    (net (code "56") (name "unconnected-(U4-RESERVED1-Pad2)") (class "Default")
      (node (ref "U4") (pin "2") (pinfunction "RESERVED1_2") (pintype "bidirectional"))
    )
    (net (code "57") (name "unconnected-(U4-RESERVED2-Pad5)") (class "Default")
      (node (ref "U4") (pin "5") (pinfunction "RESERVED2_5") (pintype "bidirectional"))
    )
    (net (code "58") (name "unconnected-(U4-RESERVED3-Pad11)") (class "Default")
      (node (ref "U4") (pin "11") (pinfunction "RESERVED3_11") (pintype "bidirectional"))
    )
    (net (code "59") (name "unconnected-(U4-RESERVED4-Pad12)") (class "Default")
      (node (ref "U4") (pin "12") (pinfunction "RESERVED4_12") (pintype "bidirectional"))
    )
    (net (code "60") (name "unconnected-(U4-RESERVED5-Pad16)") (class "Default")
      (node (ref "U4") (pin "16") (pinfunction "RESERVED5_16") (pintype "bidirectional"))
    )
    (net (code "61") (name "unconnected-(U4-RESERVED6-Pad19)") (class "Default")
      (node (ref "U4") (pin "19") (pinfunction "RESERVED6_19") (pintype "bidirectional"))
    )
    (net (code "62") (name "unconnected-(U4-RESERVED7-Pad20)") (class "Default")
      (node (ref "U4") (pin "20") (pinfunction "RESERVED7_20") (pintype "bidirectional"))
    )
    (net (code "63") (name "unconnected-(U4-RXD-A-Pad15)") (class "Default")
      (node (ref "U4") (pin "15") (pinfunction "RXD-A_15") (pintype "bidirectional"))
    )
    (net (code "64") (name "unconnected-(U4-SHORT-Pad4)") (class "Default")
      (node (ref "U4") (pin "4") (pinfunction "SHORT_4") (pintype "bidirectional"))
    )
    (net (code "65") (name "unconnected-(U4-TXD-A-Pad17)") (class "Default")
      (node (ref "U4") (pin "17") (pinfunction "TXD-A_17") (pintype "bidirectional"))
    )
    (net (code "66") (name "unconnected-(U4-XRESET-Pad7)") (class "Default")
      (node (ref "U4") (pin "7") (pinfunction "XRESET_7") (pintype "bidirectional"))
    )
    (net (code "67") (name "unconnected-(U5-Pad7)") (class "Default")
      (node (ref "U5") (pin "7") (pinfunction "7_7") (pintype "bidirectional"))
    )
    (net (code "68") (name "unconnected-(U5-Pad8)") (class "Default")
      (node (ref "U5") (pin "8") (pinfunction "8_8") (pintype "bidirectional"))
    )
    (net (code "69") (name "unconnected-(U5-PadPGM)") (class "Default")
      (node (ref "U5") (pin "PGM") (pinfunction "PGM_PGM") (pintype "bidirectional"))
    )
    (net (code "70") (name "unconnected-(U5-PadVBAT)") (class "Default")
      (node (ref "U5") (pin "VBAT") (pinfunction "VBAT_VBAT") (pintype "no_connect"))
    )
    (net (code "71") (name "unconnected-(U5-RESET-PadRESET{slash}A14{slash}DAC)") (class "Default")
      (node (ref "U5") (pin "RESET/A14/DAC") (pinfunction "RESET_RESET/A14/DAC") (pintype "bidirectional"))
    )
  )
)
